# LPCB230_-_OVERVIEW.net
KiCad netlist of a schematic drawn in Altium Designer
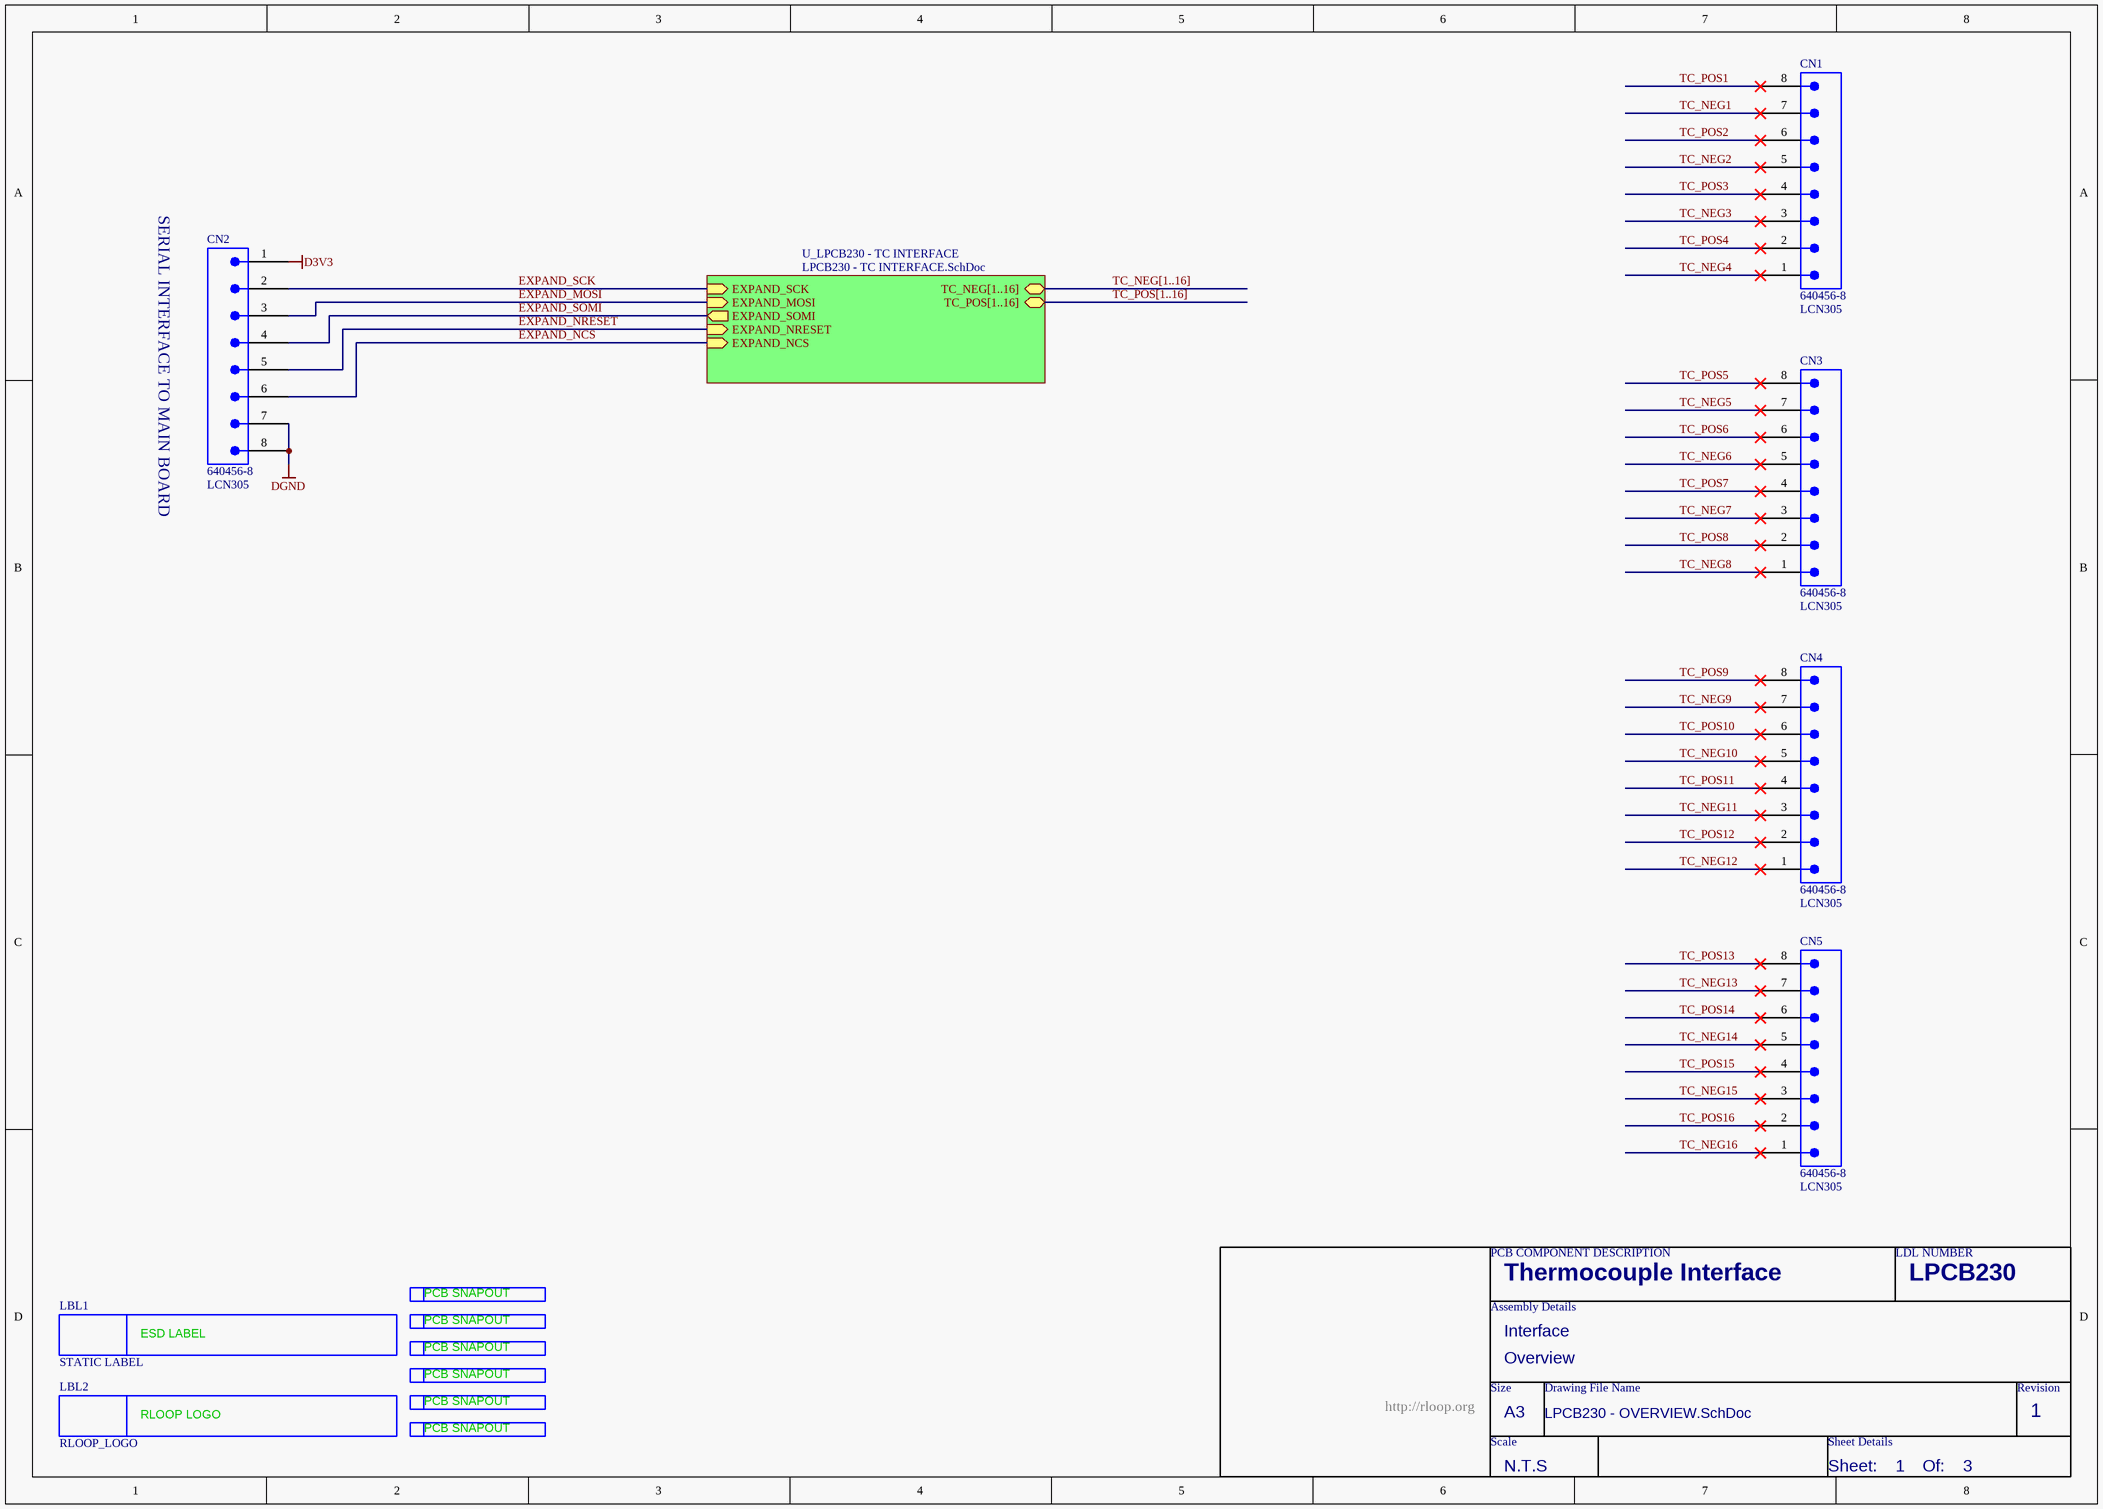
[diagram p0: LPCB230 - OVERVIEW.SchDoc]

(export (version "E")
  (design (tool "Eeschema 10.0.6"))
  (components
    (comp (ref "CN1")
      (value "640456-8")
      (footprint "640456-8")
      (description "Connector, Male Header, 8 Way")
      (fields (field (name "LDL_NUMBER") "LCN305"))
      (libsource (lib "LDL_Connectors") (part "640456-8"))
    )
    (comp (ref "CN2")
      (value "640456-8")
      (footprint "640456-8")
      (description "Connector, Male Header, 8 Way")
      (fields (field (name "LDL_NUMBER") "LCN305"))
      (libsource (lib "LDL_Connectors") (part "640456-8"))
    )
    (comp (ref "CN3")
      (value "640456-8")
      (footprint "640456-8")
      (description "Connector, Male Header, 8 Way")
      (fields (field (name "LDL_NUMBER") "LCN305"))
      (libsource (lib "LDL_Connectors") (part "640456-8"))
    )
    (comp (ref "CN4")
      (value "640456-8")
      (footprint "640456-8")
      (description "Connector, Male Header, 8 Way")
      (fields (field (name "LDL_NUMBER") "LCN305"))
      (libsource (lib "LDL_Connectors") (part "640456-8"))
    )
    (comp (ref "CN5")
      (value "640456-8")
      (footprint "640456-8")
      (description "Connector, Male Header, 8 Way")
      (fields (field (name "LDL_NUMBER") "LCN305"))
      (libsource (lib "LDL_Connectors") (part "640456-8"))
    )
    (comp (ref "LBL1")
      (value "STATIC LABEL")
      (footprint "STATIC_LABEL")
      (libsource (lib "LDL_Mechanical") (part "STATIC LABEL"))
    )
    (comp (ref "LBL2")
      (value "RLOOP_LOGO")
      (footprint "RLOOP_LOGO")
      (libsource (lib "LDL_Mechanical") (part "RLOOP_LOGO"))
    )
    (comp (ref "SN1")
      (value "PCB_SNAPOUT")
      (footprint "SNAPOUT_NEW")
      (libsource (lib "LDL_Mechanical") (part "PCB_SNAPOUT"))
    )
    (comp (ref "SN2")
      (value "PCB_SNAPOUT")
      (footprint "SNAPOUT_NEW")
      (libsource (lib "LDL_Mechanical") (part "PCB_SNAPOUT"))
    )
    (comp (ref "SN3")
      (value "PCB_SNAPOUT")
      (footprint "SNAPOUT_NEW")
      (libsource (lib "LDL_Mechanical") (part "PCB_SNAPOUT"))
    )
    (comp (ref "SN4")
      (value "PCB_SNAPOUT")
      (footprint "SNAPOUT_NEW")
      (libsource (lib "LDL_Mechanical") (part "PCB_SNAPOUT"))
    )
    (comp (ref "SN5")
      (value "PCB_SNAPOUT")
      (footprint "SNAPOUT_NEW")
      (libsource (lib "LDL_Mechanical") (part "PCB_SNAPOUT"))
    )
    (comp (ref "SN6")
      (value "PCB_SNAPOUT")
      (footprint "SNAPOUT_NEW")
      (libsource (lib "LDL_Mechanical") (part "PCB_SNAPOUT"))
    )
  )
  (nets
    (net (code "1") (name "/EXPAND_MOSI") (class "Default")
      (node (ref "CN2") (pin "3") (pinfunction "3_3") (pintype "passive"))
    )
    (net (code "2") (name "/EXPAND_NCS") (class "Default")
      (node (ref "CN2") (pin "6") (pinfunction "6_6") (pintype "passive"))
    )
    (net (code "3") (name "/EXPAND_NRESET") (class "Default")
      (node (ref "CN2") (pin "5") (pinfunction "5_5") (pintype "passive"))
    )
    (net (code "4") (name "/EXPAND_SCK") (class "Default")
      (node (ref "CN2") (pin "2") (pinfunction "2_2") (pintype "passive"))
    )
    (net (code "5") (name "/EXPAND_SOMI") (class "Default")
      (node (ref "CN2") (pin "4") (pinfunction "4_4") (pintype "passive"))
    )
    (net (code "6") (name "/TC_NEG1") (class "Default")
      (node (ref "CN1") (pin "7") (pinfunction "7_7") (pintype "passive+no_connect"))
    )
    (net (code "7") (name "/TC_NEG2") (class "Default")
      (node (ref "CN1") (pin "5") (pinfunction "5_5") (pintype "passive+no_connect"))
    )
    (net (code "8") (name "/TC_NEG3") (class "Default")
      (node (ref "CN1") (pin "3") (pinfunction "3_3") (pintype "passive+no_connect"))
    )
    (net (code "9") (name "/TC_NEG4") (class "Default")
      (node (ref "CN1") (pin "1") (pinfunction "1_1") (pintype "passive+no_connect"))
    )
    (net (code "10") (name "/TC_NEG5") (class "Default")
      (node (ref "CN3") (pin "7") (pinfunction "7_7") (pintype "passive+no_connect"))
    )
    (net (code "11") (name "/TC_NEG6") (class "Default")
      (node (ref "CN3") (pin "5") (pinfunction "5_5") (pintype "passive+no_connect"))
    )
    (net (code "12") (name "/TC_NEG7") (class "Default")
      (node (ref "CN3") (pin "3") (pinfunction "3_3") (pintype "passive+no_connect"))
    )
    (net (code "13") (name "/TC_NEG8") (class "Default")
      (node (ref "CN3") (pin "1") (pinfunction "1_1") (pintype "passive+no_connect"))
    )
    (net (code "14") (name "/TC_NEG9") (class "Default")
      (node (ref "CN4") (pin "7") (pinfunction "7_7") (pintype "passive+no_connect"))
    )
    (net (code "15") (name "/TC_NEG10") (class "Default")
      (node (ref "CN4") (pin "5") (pinfunction "5_5") (pintype "passive+no_connect"))
    )
    (net (code "16") (name "/TC_NEG11") (class "Default")
      (node (ref "CN4") (pin "3") (pinfunction "3_3") (pintype "passive+no_connect"))
    )
    (net (code "17") (name "/TC_NEG12") (class "Default")
      (node (ref "CN4") (pin "1") (pinfunction "1_1") (pintype "passive+no_connect"))
    )
    (net (code "18") (name "/TC_NEG13") (class "Default")
      (node (ref "CN5") (pin "7") (pinfunction "7_7") (pintype "passive+no_connect"))
    )
    (net (code "19") (name "/TC_NEG14") (class "Default")
      (node (ref "CN5") (pin "5") (pinfunction "5_5") (pintype "passive+no_connect"))
    )
    (net (code "20") (name "/TC_NEG15") (class "Default")
      (node (ref "CN5") (pin "3") (pinfunction "3_3") (pintype "passive+no_connect"))
    )
    (net (code "21") (name "/TC_NEG16") (class "Default")
      (node (ref "CN5") (pin "1") (pinfunction "1_1") (pintype "passive+no_connect"))
    )
    (net (code "23") (name "/TC_POS1") (class "Default")
      (node (ref "CN1") (pin "8") (pinfunction "8_8") (pintype "passive+no_connect"))
    )
    (net (code "24") (name "/TC_POS2") (class "Default")
      (node (ref "CN1") (pin "6") (pinfunction "6_6") (pintype "passive+no_connect"))
    )
    (net (code "25") (name "/TC_POS3") (class "Default")
      (node (ref "CN1") (pin "4") (pinfunction "4_4") (pintype "passive+no_connect"))
    )
    (net (code "26") (name "/TC_POS4") (class "Default")
      (node (ref "CN1") (pin "2") (pinfunction "2_2") (pintype "passive+no_connect"))
    )
    (net (code "27") (name "/TC_POS5") (class "Default")
      (node (ref "CN3") (pin "8") (pinfunction "8_8") (pintype "passive+no_connect"))
    )
    (net (code "28") (name "/TC_POS6") (class "Default")
      (node (ref "CN3") (pin "6") (pinfunction "6_6") (pintype "passive+no_connect"))
    )
    (net (code "29") (name "/TC_POS7") (class "Default")
      (node (ref "CN3") (pin "4") (pinfunction "4_4") (pintype "passive+no_connect"))
    )
    (net (code "30") (name "/TC_POS8") (class "Default")
      (node (ref "CN3") (pin "2") (pinfunction "2_2") (pintype "passive+no_connect"))
    )
    (net (code "31") (name "/TC_POS9") (class "Default")
      (node (ref "CN4") (pin "8") (pinfunction "8_8") (pintype "passive+no_connect"))
    )
    (net (code "32") (name "/TC_POS10") (class "Default")
      (node (ref "CN4") (pin "6") (pinfunction "6_6") (pintype "passive+no_connect"))
    )
    (net (code "33") (name "/TC_POS11") (class "Default")
      (node (ref "CN4") (pin "4") (pinfunction "4_4") (pintype "passive+no_connect"))
    )
    (net (code "34") (name "/TC_POS12") (class "Default")
      (node (ref "CN4") (pin "2") (pinfunction "2_2") (pintype "passive+no_connect"))
    )
    (net (code "35") (name "/TC_POS13") (class "Default")
      (node (ref "CN5") (pin "8") (pinfunction "8_8") (pintype "passive+no_connect"))
    )
    (net (code "36") (name "/TC_POS14") (class "Default")
      (node (ref "CN5") (pin "6") (pinfunction "6_6") (pintype "passive+no_connect"))
    )
    (net (code "37") (name "/TC_POS15") (class "Default")
      (node (ref "CN5") (pin "4") (pinfunction "4_4") (pintype "passive+no_connect"))
    )
    (net (code "38") (name "/TC_POS16") (class "Default")
      (node (ref "CN5") (pin "2") (pinfunction "2_2") (pintype "passive+no_connect"))
    )
    (net (code "40") (name "D3V3") (class "Default")
      (node (ref "CN2") (pin "1") (pinfunction "1_1") (pintype "passive"))
    )
    (net (code "41") (name "DGND") (class "Default")
      (node (ref "CN2") (pin "7") (pinfunction "7_7") (pintype "passive"))
      (node (ref "CN2") (pin "8") (pinfunction "8_8") (pintype "passive"))
    )
  )
)
